# fpga.net
KiCad netlist of a schematic drawn in Altium Designer
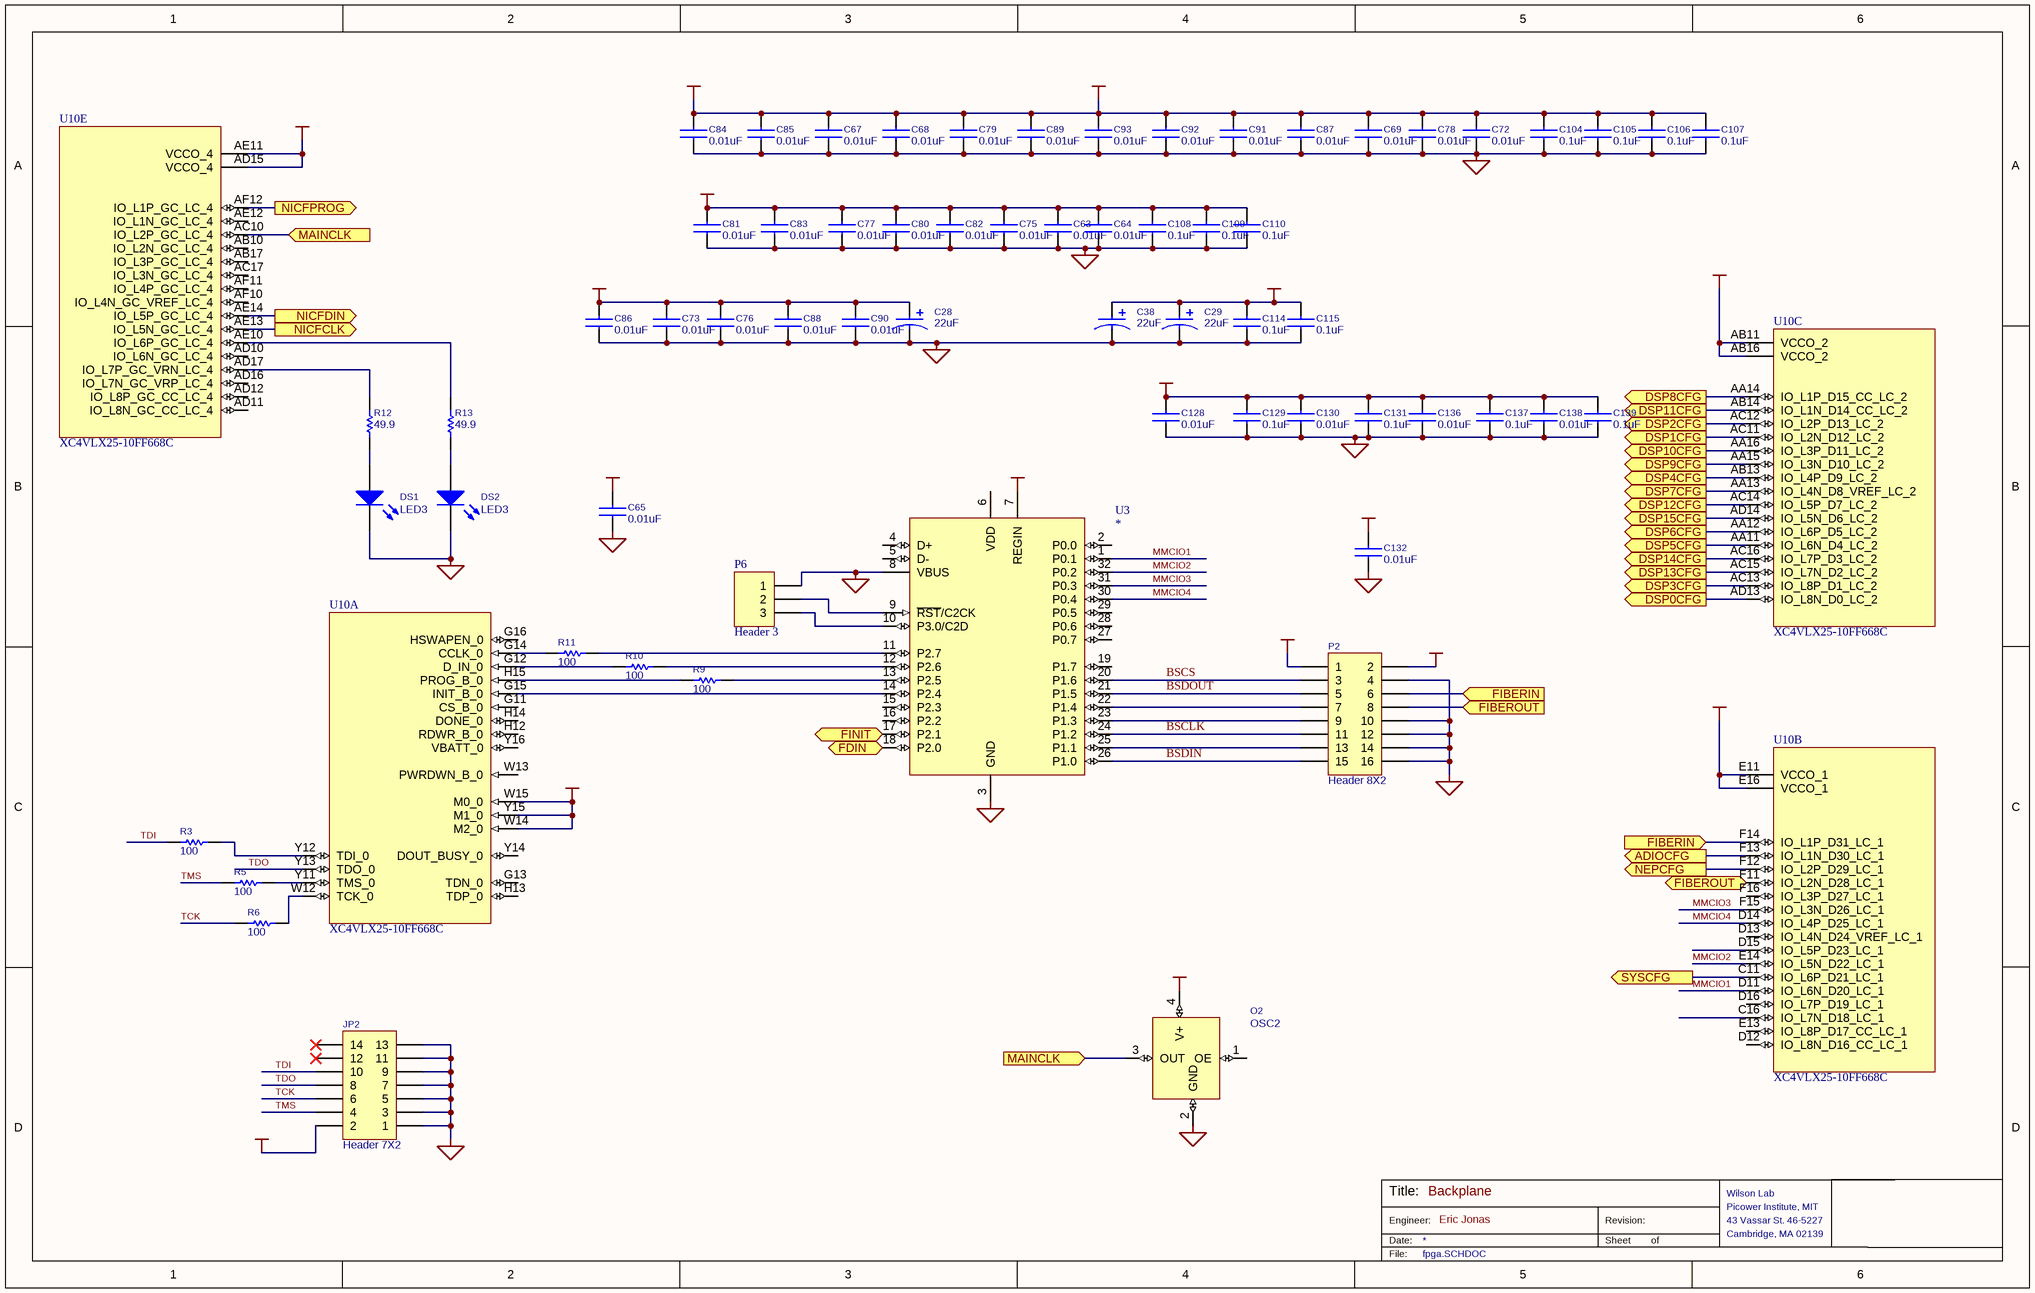
[diagram p0: fpga.SCHDOC]

(export (version "E")
  (design (tool "Eeschema 10.0.6"))
  (components
    (comp (ref "C28")
      (value "22uF")
      (footprint "6032")
      (description "Standard Capacitor")
      (fields (field (name "Comment") "POLCAP2"))
      (libsource (lib "parts") (part "POLCAP2"))
    )
    (comp (ref "C29")
      (value "22uF")
      (footprint "6032")
      (description "Standard Capacitor")
      (fields (field (name "Comment") "POLCAP2"))
      (libsource (lib "parts") (part "POLCAP2"))
    )
    (comp (ref "C38")
      (value "22uF")
      (footprint "6032")
      (description "Standard Capacitor")
      (fields (field (name "Comment") "POLCAP2"))
      (libsource (lib "parts") (part "POLCAP2"))
    )
    (comp (ref "C63")
      (value "0.01uF")
      (footprint "0402")
      (description "Standard Capacitor")
      (fields (field (name "Comment") "CAPACITOR"))
      (libsource (lib "parts") (part "CAPACITOR"))
    )
    (comp (ref "C64")
      (value "0.01uF")
      (footprint "0402")
      (description "Standard Capacitor")
      (fields (field (name "Comment") "CAPACITOR"))
      (libsource (lib "parts") (part "CAPACITOR"))
    )
    (comp (ref "C65")
      (value "0.01uF")
      (footprint "0402")
      (description "Standard Capacitor")
      (fields (field (name "Comment") "CAPACITOR"))
      (libsource (lib "parts") (part "CAPACITOR"))
    )
    (comp (ref "C67")
      (value "0.01uF")
      (footprint "0402")
      (description "Standard Capacitor")
      (fields (field (name "Comment") "CAPACITOR"))
      (libsource (lib "parts") (part "CAPACITOR"))
    )
    (comp (ref "C68")
      (value "0.01uF")
      (footprint "0402")
      (description "Standard Capacitor")
      (fields (field (name "Comment") "CAPACITOR"))
      (libsource (lib "parts") (part "CAPACITOR"))
    )
    (comp (ref "C69")
      (value "0.01uF")
      (footprint "0402")
      (description "Standard Capacitor")
      (fields (field (name "Comment") "CAPACITOR"))
      (libsource (lib "parts") (part "CAPACITOR"))
    )
    (comp (ref "C72")
      (value "0.01uF")
      (footprint "0402")
      (description "Standard Capacitor")
      (fields (field (name "Comment") "CAPACITOR"))
      (libsource (lib "parts") (part "CAPACITOR"))
    )
    (comp (ref "C73")
      (value "0.01uF")
      (footprint "0402")
      (description "Standard Capacitor")
      (fields (field (name "Comment") "CAPACITOR"))
      (libsource (lib "parts") (part "CAPACITOR"))
    )
    (comp (ref "C75")
      (value "0.01uF")
      (footprint "0402")
      (description "Standard Capacitor")
      (fields (field (name "Comment") "CAPACITOR"))
      (libsource (lib "parts") (part "CAPACITOR"))
    )
    (comp (ref "C76")
      (value "0.01uF")
      (footprint "0402")
      (description "Standard Capacitor")
      (fields (field (name "Comment") "CAPACITOR"))
      (libsource (lib "parts") (part "CAPACITOR"))
    )
    (comp (ref "C77")
      (value "0.01uF")
      (footprint "0402")
      (description "Standard Capacitor")
      (fields (field (name "Comment") "CAPACITOR"))
      (libsource (lib "parts") (part "CAPACITOR"))
    )
    (comp (ref "C78")
      (value "0.01uF")
      (footprint "0402")
      (description "Standard Capacitor")
      (fields (field (name "Comment") "CAPACITOR"))
      (libsource (lib "parts") (part "CAPACITOR"))
    )
    (comp (ref "C79")
      (value "0.01uF")
      (footprint "0402")
      (description "Standard Capacitor")
      (fields (field (name "Comment") "CAPACITOR"))
      (libsource (lib "parts") (part "CAPACITOR"))
    )
    (comp (ref "C80")
      (value "0.01uF")
      (footprint "0402")
      (description "Standard Capacitor")
      (fields (field (name "Comment") "CAPACITOR"))
      (libsource (lib "parts") (part "CAPACITOR"))
    )
    (comp (ref "C81")
      (value "0.01uF")
      (footprint "0402")
      (description "Standard Capacitor")
      (fields (field (name "Comment") "CAPACITOR"))
      (libsource (lib "parts") (part "CAPACITOR"))
    )
    (comp (ref "C82")
      (value "0.01uF")
      (footprint "0402")
      (description "Standard Capacitor")
      (fields (field (name "Comment") "CAPACITOR"))
      (libsource (lib "parts") (part "CAPACITOR"))
    )
    (comp (ref "C83")
      (value "0.01uF")
      (footprint "0402")
      (description "Standard Capacitor")
      (fields (field (name "Comment") "CAPACITOR"))
      (libsource (lib "parts") (part "CAPACITOR"))
    )
    (comp (ref "C84")
      (value "0.01uF")
      (footprint "0402")
      (description "Standard Capacitor")
      (fields (field (name "Comment") "CAPACITOR"))
      (libsource (lib "parts") (part "CAPACITOR"))
    )
    (comp (ref "C85")
      (value "0.01uF")
      (footprint "0402")
      (description "Standard Capacitor")
      (fields (field (name "Comment") "CAPACITOR"))
      (libsource (lib "parts") (part "CAPACITOR"))
    )
    (comp (ref "C86")
      (value "0.01uF")
      (footprint "0402")
      (description "Standard Capacitor")
      (fields (field (name "Comment") "CAPACITOR"))
      (libsource (lib "parts") (part "CAPACITOR"))
    )
    (comp (ref "C87")
      (value "0.01uF")
      (footprint "0402")
      (description "Standard Capacitor")
      (fields (field (name "Comment") "CAPACITOR"))
      (libsource (lib "parts") (part "CAPACITOR"))
    )
    (comp (ref "C88")
      (value "0.01uF")
      (footprint "0402")
      (description "Standard Capacitor")
      (fields (field (name "Comment") "CAPACITOR"))
      (libsource (lib "parts") (part "CAPACITOR"))
    )
    (comp (ref "C89")
      (value "0.01uF")
      (footprint "0402")
      (description "Standard Capacitor")
      (fields (field (name "Comment") "CAPACITOR"))
      (libsource (lib "parts") (part "CAPACITOR"))
    )
    (comp (ref "C90")
      (value "0.01uF")
      (footprint "0402")
      (description "Standard Capacitor")
      (fields (field (name "Comment") "CAPACITOR"))
      (libsource (lib "parts") (part "CAPACITOR"))
    )
    (comp (ref "C91")
      (value "0.01uF")
      (footprint "0402")
      (description "Standard Capacitor")
      (fields (field (name "Comment") "CAPACITOR"))
      (libsource (lib "parts") (part "CAPACITOR"))
    )
    (comp (ref "C92")
      (value "0.01uF")
      (footprint "0402")
      (description "Standard Capacitor")
      (fields (field (name "Comment") "CAPACITOR"))
      (libsource (lib "parts") (part "CAPACITOR"))
    )
    (comp (ref "C93")
      (value "0.01uF")
      (footprint "0402")
      (description "Standard Capacitor")
      (fields (field (name "Comment") "CAPACITOR"))
      (libsource (lib "parts") (part "CAPACITOR"))
    )
    (comp (ref "C104")
      (value "0.1uF")
      (footprint "0603")
      (description "Standard Capacitor")
      (fields (field (name "Comment") "CAPACITOR"))
      (libsource (lib "parts") (part "CAPACITOR"))
    )
    (comp (ref "C105")
      (value "0.1uF")
      (footprint "0603")
      (description "Standard Capacitor")
      (fields (field (name "Comment") "CAPACITOR"))
      (libsource (lib "parts") (part "CAPACITOR"))
    )
    (comp (ref "C106")
      (value "0.1uF")
      (footprint "0603")
      (description "Standard Capacitor")
      (fields (field (name "Comment") "CAPACITOR"))
      (libsource (lib "parts") (part "CAPACITOR"))
    )
    (comp (ref "C107")
      (value "0.1uF")
      (footprint "0603")
      (description "Standard Capacitor")
      (fields (field (name "Comment") "CAPACITOR"))
      (libsource (lib "parts") (part "CAPACITOR"))
    )
    (comp (ref "C108")
      (value "0.1uF")
      (footprint "0603")
      (description "Standard Capacitor")
      (fields (field (name "Comment") "CAPACITOR"))
      (libsource (lib "parts") (part "CAPACITOR"))
    )
    (comp (ref "C109")
      (value "0.1uF")
      (footprint "0603")
      (description "Standard Capacitor")
      (fields (field (name "Comment") "CAPACITOR"))
      (libsource (lib "parts") (part "CAPACITOR"))
    )
    (comp (ref "C110")
      (value "0.1uF")
      (footprint "0603")
      (description "Standard Capacitor")
      (fields (field (name "Comment") "CAPACITOR"))
      (libsource (lib "parts") (part "CAPACITOR"))
    )
    (comp (ref "C114")
      (value "0.1uF")
      (footprint "0603")
      (description "Standard Capacitor")
      (fields (field (name "Comment") "CAPACITOR"))
      (libsource (lib "parts") (part "CAPACITOR"))
    )
    (comp (ref "C115")
      (value "0.1uF")
      (footprint "0603")
      (description "Standard Capacitor")
      (fields (field (name "Comment") "CAPACITOR"))
      (libsource (lib "parts") (part "CAPACITOR"))
    )
    (comp (ref "C128")
      (value "0.01uF")
      (footprint "0402")
      (description "Standard Capacitor")
      (fields (field (name "Comment") "CAPACITOR"))
      (libsource (lib "parts") (part "CAPACITOR"))
    )
    (comp (ref "C129")
      (value "0.1uF")
      (footprint "0603")
      (description "Standard Capacitor")
      (fields (field (name "Comment") "CAPACITOR"))
      (libsource (lib "parts") (part "CAPACITOR"))
    )
    (comp (ref "C130")
      (value "0.01uF")
      (footprint "0402")
      (description "Standard Capacitor")
      (fields (field (name "Comment") "CAPACITOR"))
      (libsource (lib "parts") (part "CAPACITOR"))
    )
    (comp (ref "C131")
      (value "0.1uF")
      (footprint "0603")
      (description "Standard Capacitor")
      (fields (field (name "Comment") "CAPACITOR"))
      (libsource (lib "parts") (part "CAPACITOR"))
    )
    (comp (ref "C132")
      (value "0.01uF")
      (footprint "0402")
      (description "Standard Capacitor")
      (fields (field (name "Comment") "CAPACITOR"))
      (libsource (lib "parts") (part "CAPACITOR"))
    )
    (comp (ref "C136")
      (value "0.01uF")
      (footprint "0402")
      (description "Standard Capacitor")
      (fields (field (name "Comment") "CAPACITOR"))
      (libsource (lib "parts") (part "CAPACITOR"))
    )
    (comp (ref "C137")
      (value "0.1uF")
      (footprint "0603")
      (description "Standard Capacitor")
      (fields (field (name "Comment") "CAPACITOR"))
      (libsource (lib "parts") (part "CAPACITOR"))
    )
    (comp (ref "C138")
      (value "0.01uF")
      (footprint "0402")
      (description "Standard Capacitor")
      (fields (field (name "Comment") "CAPACITOR"))
      (libsource (lib "parts") (part "CAPACITOR"))
    )
    (comp (ref "C139")
      (value "0.1uF")
      (footprint "0603")
      (description "Standard Capacitor")
      (fields (field (name "Comment") "CAPACITOR"))
      (libsource (lib "parts") (part "CAPACITOR"))
    )
    (comp (ref "DS1")
      (value "LED3")
      (footprint "SMD _LED")
      (description "Typical BLUE SiC LED")
      (fields (field (name "PUBLISHER") "Altium Limited"))
      (libsource (lib "Miscellaneous Devices") (part "LED3"))
    )
    (comp (ref "DS2")
      (value "LED3")
      (footprint "SMD _LED")
      (description "Typical BLUE SiC LED")
      (fields (field (name "PUBLISHER") "Altium Limited"))
      (libsource (lib "Miscellaneous Devices") (part "LED3"))
    )
    (comp (ref "JP2")
      (value "Header 7X2")
      (footprint "SMT 2x7 2mm HDR")
      (description "Header, 7-Pin, Dual row")
      (fields (field (name "MANUFACTURER") "Generic Components") (field (name "PUBLISHER") "Altium Limited"))
      (libsource (lib "Miscellaneous Connectors") (part "Header 7X2"))
    )
    (comp (ref "O2")
      (value "OSC2")
      (footprint "ECS-3953M")
      (description "ECS SMD Oscillator, ECS-3953M")
      (fields (field (name "PART") "SG-636PCE 30.0000MC0"))
      (libsource (lib "parts") (part "OSC2"))
    )
    (comp (ref "P2")
      (value "Header 8X2")
      (footprint "MOLEX 15-91-2160")
      (description "Header, 8-Pin, Dual row")
      (fields (field (name "PUBLISHER") "Altium Limited"))
      (libsource (lib "parts") (part "Header 8X2"))
    )
    (comp (ref "P6")
      (value "Header 3")
      (footprint "HDR1X3")
      (description "Header, 3-Pin")
      (fields (field (name "PUBLISHER") "Altium Limited"))
      (libsource (lib "Miscellaneous Connectors") (part "Header 3"))
    )
    (comp (ref "R3")
      (value "100")
      (footprint "0603")
      (description "Standard Passive Resistor")
      (fields (field (name "TOLERANCE") "1%") (field (name "Comment") "current-limiting series res"))
      (libsource (lib "parts") (part "RESISTOR"))
    )
    (comp (ref "R5")
      (value "100")
      (footprint "0603")
      (description "Standard Passive Resistor")
      (fields (field (name "TOLERANCE") "1%") (field (name "Comment") "current-limiting series res"))
      (libsource (lib "parts") (part "RESISTOR"))
    )
    (comp (ref "R6")
      (value "100")
      (footprint "0603")
      (description "Standard Passive Resistor")
      (fields (field (name "TOLERANCE") "1%") (field (name "Comment") "current-limiting series res"))
      (libsource (lib "parts") (part "RESISTOR"))
    )
    (comp (ref "R9")
      (value "100")
      (footprint "0603")
      (description "Standard Passive Resistor")
      (fields (field (name "TOLERANCE") "1%") (field (name "Comment") "RESISTOR"))
      (libsource (lib "parts") (part "RESISTOR"))
    )
    (comp (ref "R10")
      (value "100")
      (footprint "0603")
      (description "Standard Passive Resistor")
      (fields (field (name "TOLERANCE") "1%") (field (name "Comment") "RESISTOR"))
      (libsource (lib "parts") (part "RESISTOR"))
    )
    (comp (ref "R11")
      (value "100")
      (footprint "0603")
      (description "Standard Passive Resistor")
      (fields (field (name "TOLERANCE") "1%") (field (name "Comment") "RESISTOR"))
      (libsource (lib "parts") (part "RESISTOR"))
    )
    (comp (ref "R12")
      (value "49.9")
      (footprint "0402")
      (description "Standard Passive Resistor")
      (fields (field (name "TOLERANCE") "1%") (field (name "Comment") "current-limiting series res"))
      (libsource (lib "parts") (part "RESISTOR"))
    )
    (comp (ref "R13")
      (value "49.9")
      (footprint "0402")
      (description "Standard Passive Resistor")
      (fields (field (name "TOLERANCE") "1%") (field (name "Comment") "current-limiting series res"))
      (libsource (lib "parts") (part "RESISTOR"))
    )
    (comp (ref "U3")
      (value "*")
      (footprint "QFP7x7-G32/N")
      (description "SiLiabs USB Micro")
      (libsource (lib "parts") (part "C8051F342/3/6/7"))
    )
    (comp (ref "U10")
      (value "XC4VLX25-10FF668C")
      (footprint "Xilinx FF668")
      (description "Xilinx Virtex-4")
      (libsource (lib "parts") (part "XC4VLX25-10FF668C"))
    )
  )
  (nets
    (net (code "1") (name "+0.9VCC") (class "Default") (node (ref "C132") (pin "1") (pintype "passive")))
    (net (code "2") (name "+1.2VCC") (class "Default")
      (node (ref "C28") (pin "1") (pintype "passive"))
      (node (ref "C73") (pin "1") (pintype "passive"))
      (node (ref "C76") (pin "1") (pintype "passive"))
      (node (ref "C86") (pin "1") (pintype "passive"))
      (node (ref "C88") (pin "1") (pintype "passive"))
      (node (ref "C90") (pin "1") (pintype "passive"))
    )
    (net (code "3") (name "+1.8VCC") (class "Default")
      (node (ref "C128") (pin "1") (pintype "passive"))
      (node (ref "C129") (pin "1") (pintype "passive"))
      (node (ref "C130") (pin "1") (pintype "passive"))
      (node (ref "C131") (pin "1") (pintype "passive"))
      (node (ref "C136") (pin "1") (pintype "passive"))
      (node (ref "C137") (pin "1") (pintype "passive"))
      (node (ref "C138") (pin "1") (pintype "passive"))
      (node (ref "C139") (pin "1") (pintype "passive"))
    )
    (net (code "4") (name "+2.5VCC") (class "Default")
      (node (ref "C104") (pin "1") (pintype "passive"))
      (node (ref "C105") (pin "1") (pintype "passive"))
      (node (ref "C106") (pin "1") (pintype "passive"))
      (node (ref "C107") (pin "1") (pintype "passive"))
      (node (ref "C114") (pin "1") (pintype "passive"))
      (node (ref "C115") (pin "1") (pintype "passive"))
      (node (ref "C29") (pin "1") (pintype "passive"))
      (node (ref "C38") (pin "1") (pintype "passive"))
      (node (ref "C67") (pin "1") (pintype "passive"))
      (node (ref "C68") (pin "1") (pintype "passive"))
      (node (ref "C69") (pin "1") (pintype "passive"))
      (node (ref "C72") (pin "1") (pintype "passive"))
      (node (ref "C78") (pin "1") (pintype "passive"))
      (node (ref "C79") (pin "1") (pintype "passive"))
      (node (ref "C84") (pin "1") (pintype "passive"))
      (node (ref "C85") (pin "1") (pintype "passive"))
      (node (ref "C87") (pin "1") (pintype "passive"))
      (node (ref "C89") (pin "1") (pintype "passive"))
      (node (ref "C91") (pin "1") (pintype "passive"))
      (node (ref "C92") (pin "1") (pintype "passive"))
      (node (ref "C93") (pin "1") (pintype "passive"))
    )
    (net (code "5") (name "+5VCC") (class "Default")
      (node (ref "C65") (pin "1") (pintype "passive"))
      (node (ref "P2") (pin "2") (pinfunction "2_2") (pintype "passive"))
      (node (ref "U3") (pin "7") (pinfunction "REGIN_7") (pintype "power_in"))
    )
    (net (code "6") (name "/ADIOCFG") (class "Default")
      (node (ref "U10") (pin "F13") (pinfunction "IO_L1N_D30_LC_1_F13") (pintype "bidirectional"))
    )
    (net (code "7") (name "/BSCLK") (class "Default")
      (node (ref "P2") (pin "11") (pinfunction "11_11") (pintype "passive"))
      (node (ref "U3") (pin "24") (pinfunction "P1.2_24") (pintype "bidirectional"))
    )
    (net (code "8") (name "/BSCS") (class "Default")
      (node (ref "P2") (pin "3") (pinfunction "3_3") (pintype "passive"))
      (node (ref "U3") (pin "20") (pinfunction "P1.6_20") (pintype "bidirectional"))
    )
    (net (code "9") (name "/BSDIN") (class "Default")
      (node (ref "P2") (pin "15") (pinfunction "15_15") (pintype "passive"))
      (node (ref "U3") (pin "26") (pinfunction "P1.0_26") (pintype "bidirectional"))
    )
    (net (code "10") (name "/BSDOUT") (class "Default")
      (node (ref "P2") (pin "5") (pinfunction "5_5") (pintype "passive"))
      (node (ref "U3") (pin "21") (pinfunction "P1.5_21") (pintype "bidirectional"))
    )
    (net (code "11") (name "/DSP0CFG") (class "Default")
      (node (ref "U10") (pin "AD13") (pinfunction "IO_L8N_D0_LC_2_AD13") (pintype "bidirectional"))
    )
    (net (code "12") (name "/DSP1CFG") (class "Default")
      (node (ref "U10") (pin "AC11") (pinfunction "IO_L2N_D12_LC_2_AC11") (pintype "bidirectional"))
    )
    (net (code "13") (name "/DSP2CFG") (class "Default")
      (node (ref "U10") (pin "AC12") (pinfunction "IO_L2P_D13_LC_2_AC12") (pintype "bidirectional"))
    )
    (net (code "14") (name "/DSP3CFG") (class "Default")
      (node (ref "U10") (pin "AC13") (pinfunction "IO_L8P_D1_LC_2_AC13") (pintype "bidirectional"))
    )
    (net (code "15") (name "/DSP4CFG") (class "Default")
      (node (ref "U10") (pin "AB13") (pinfunction "IO_L4P_D9_LC_2_AB13") (pintype "bidirectional"))
    )
    (net (code "16") (name "/DSP5CFG") (class "Default")
      (node (ref "U10") (pin "AA11") (pinfunction "IO_L6N_D4_LC_2_AA11") (pintype "bidirectional"))
    )
    (net (code "17") (name "/DSP6CFG") (class "Default")
      (node (ref "U10") (pin "AA12") (pinfunction "IO_L6P_D5_LC_2_AA12") (pintype "bidirectional"))
    )
    (net (code "18") (name "/DSP7CFG") (class "Default")
      (node (ref "U10") (pin "AA13") (pinfunction "IO_L4N_D8_VREF_LC_2_AA13") (pintype "bidirectional"))
    )
    (net (code "19") (name "/DSP8CFG") (class "Default")
      (node (ref "U10") (pin "AA14") (pinfunction "IO_L1P_D15_CC_LC_2_AA14") (pintype "bidirectional"))
    )
    (net (code "20") (name "/DSP9CFG") (class "Default")
      (node (ref "U10") (pin "AA15") (pinfunction "IO_L3N_D10_LC_2_AA15") (pintype "bidirectional"))
    )
    (net (code "21") (name "/DSP10CFG") (class "Default")
      (node (ref "U10") (pin "AA16") (pinfunction "IO_L3P_D11_LC_2_AA16") (pintype "bidirectional"))
    )
    (net (code "22") (name "/DSP11CFG") (class "Default")
      (node (ref "U10") (pin "AB14") (pinfunction "IO_L1N_D14_CC_LC_2_AB14") (pintype "bidirectional"))
    )
    (net (code "23") (name "/DSP12CFG") (class "Default")
      (node (ref "U10") (pin "AC14") (pinfunction "IO_L5P_D7_LC_2_AC14") (pintype "bidirectional"))
    )
    (net (code "24") (name "/DSP13CFG") (class "Default")
      (node (ref "U10") (pin "AC15") (pinfunction "IO_L7N_D2_LC_2_AC15") (pintype "bidirectional"))
    )
    (net (code "25") (name "/DSP14CFG") (class "Default")
      (node (ref "U10") (pin "AC16") (pinfunction "IO_L7P_D3_LC_2_AC16") (pintype "bidirectional"))
    )
    (net (code "26") (name "/DSP15CFG") (class "Default")
      (node (ref "U10") (pin "AD14") (pinfunction "IO_L5N_D6_LC_2_AD14") (pintype "bidirectional"))
    )
    (net (code "27") (name "/FDIN") (class "Default")
      (node (ref "U3") (pin "18") (pinfunction "P2.0_18") (pintype "bidirectional"))
    )
    (net (code "28") (name "/FIBERIN") (class "Default")
      (node (ref "P2") (pin "6") (pinfunction "6_6") (pintype "passive"))
      (node (ref "U10") (pin "F14") (pinfunction "IO_L1P_D31_LC_1_F14") (pintype "bidirectional"))
    )
    (net (code "29") (name "/FIBEROUT") (class "Default")
      (node (ref "P2") (pin "8") (pinfunction "8_8") (pintype "passive"))
      (node (ref "U10") (pin "F11") (pinfunction "IO_L2N_D28_LC_1_F11") (pintype "bidirectional"))
    )
    (net (code "30") (name "/FINIT") (class "Default")
      (node (ref "U3") (pin "17") (pinfunction "P2.1_17") (pintype "bidirectional"))
    )
    (net (code "31") (name "/MAINCLK") (class "Default")
      (node (ref "O2") (pin "3") (pinfunction "OUT_3") (pintype "bidirectional"))
      (node (ref "U10") (pin "AC10") (pinfunction "IO_L2P_GC_LC_4_AC10") (pintype "bidirectional"))
    )
    (net (code "32") (name "/MMCIO1") (class "Default")
      (node (ref "U10") (pin "D11") (pinfunction "IO_L6N_D20_LC_1_D11") (pintype "bidirectional"))
      (node (ref "U3") (pin "1") (pinfunction "P0.1_1") (pintype "bidirectional"))
    )
    (net (code "33") (name "/MMCIO2") (class "Default")
      (node (ref "U10") (pin "E14") (pinfunction "IO_L5N_D22_LC_1_E14") (pintype "bidirectional"))
      (node (ref "U3") (pin "32") (pinfunction "P0.2_32") (pintype "bidirectional"))
    )
    (net (code "34") (name "/MMCIO3") (class "Default")
      (node (ref "U10") (pin "F15") (pinfunction "IO_L3N_D26_LC_1_F15") (pintype "bidirectional"))
      (node (ref "U3") (pin "31") (pinfunction "P0.3_31") (pintype "bidirectional"))
    )
    (net (code "35") (name "/MMCIO4") (class "Default")
      (node (ref "U10") (pin "D14") (pinfunction "IO_L4P_D25_LC_1_D14") (pintype "bidirectional"))
      (node (ref "U3") (pin "30") (pinfunction "P0.4_30") (pintype "bidirectional"))
    )
    (net (code "36") (name "/NEPCFG") (class "Default")
      (node (ref "U10") (pin "F12") (pinfunction "IO_L2P_D29_LC_1_F12") (pintype "bidirectional"))
    )
    (net (code "37") (name "/NICFCLK") (class "Default")
      (node (ref "U10") (pin "AE13") (pinfunction "IO_L5N_GC_LC_4_AE13") (pintype "bidirectional"))
    )
    (net (code "38") (name "/NICFDIN") (class "Default")
      (node (ref "U10") (pin "AE14") (pinfunction "IO_L5P_GC_LC_4_AE14") (pintype "bidirectional"))
    )
    (net (code "39") (name "/NICFPROG") (class "Default")
      (node (ref "U10") (pin "AF12") (pinfunction "IO_L1P_GC_LC_4_AF12") (pintype "bidirectional"))
    )
    (net (code "40") (name "/SYSCFG") (class "Default")
      (node (ref "U10") (pin "C11") (pinfunction "IO_L6P_D21_LC_1_C11") (pintype "bidirectional"))
    )
    (net (code "41") (name "/TCK") (class "Default")
      (node (ref "JP2") (pin "6") (pinfunction "6_6") (pintype "passive"))
      (node (ref "R6") (pin "1") (pintype "passive"))
    )
    (net (code "42") (name "/TDI") (class "Default")
      (node (ref "JP2") (pin "10") (pinfunction "10_10") (pintype "passive"))
      (node (ref "R3") (pin "2") (pintype "passive"))
    )
    (net (code "43") (name "/TDO") (class "Default")
      (node (ref "JP2") (pin "8") (pinfunction "8_8") (pintype "passive"))
      (node (ref "U10") (pin "Y13") (pinfunction "TDO_0_Y13") (pintype "bidirectional"))
    )
    (net (code "44") (name "/TMS") (class "Default")
      (node (ref "JP2") (pin "4") (pinfunction "4_4") (pintype "passive"))
      (node (ref "R5") (pin "2") (pintype "passive"))
    )
    (net (code "45") (name "GND") (class "Default")
      (node (ref "C104") (pin "2") (pintype "passive"))
      (node (ref "C105") (pin "2") (pintype "passive"))
      (node (ref "C106") (pin "2") (pintype "passive"))
      (node (ref "C107") (pin "2") (pintype "passive"))
      (node (ref "C108") (pin "2") (pintype "passive"))
      (node (ref "C109") (pin "2") (pintype "passive"))
      (node (ref "C110") (pin "2") (pintype "passive"))
      (node (ref "C114") (pin "2") (pintype "passive"))
      (node (ref "C115") (pin "2") (pintype "passive"))
      (node (ref "C128") (pin "2") (pintype "passive"))
      (node (ref "C129") (pin "2") (pintype "passive"))
      (node (ref "C130") (pin "2") (pintype "passive"))
      (node (ref "C131") (pin "2") (pintype "passive"))
      (node (ref "C132") (pin "2") (pintype "passive"))
      (node (ref "C136") (pin "2") (pintype "passive"))
      (node (ref "C137") (pin "2") (pintype "passive"))
      (node (ref "C138") (pin "2") (pintype "passive"))
      (node (ref "C139") (pin "2") (pintype "passive"))
      (node (ref "C28") (pin "2") (pintype "passive"))
      (node (ref "C29") (pin "2") (pintype "passive"))
      (node (ref "C38") (pin "2") (pintype "passive"))
      (node (ref "C63") (pin "2") (pintype "passive"))
      (node (ref "C64") (pin "2") (pintype "passive"))
      (node (ref "C65") (pin "2") (pintype "passive"))
      (node (ref "C67") (pin "2") (pintype "passive"))
      (node (ref "C68") (pin "2") (pintype "passive"))
      (node (ref "C69") (pin "2") (pintype "passive"))
      (node (ref "C72") (pin "2") (pintype "passive"))
      (node (ref "C73") (pin "2") (pintype "passive"))
      (node (ref "C75") (pin "2") (pintype "passive"))
      (node (ref "C76") (pin "2") (pintype "passive"))
      (node (ref "C77") (pin "2") (pintype "passive"))
      (node (ref "C78") (pin "2") (pintype "passive"))
      (node (ref "C79") (pin "2") (pintype "passive"))
      (node (ref "C80") (pin "2") (pintype "passive"))
      (node (ref "C81") (pin "2") (pintype "passive"))
      (node (ref "C82") (pin "2") (pintype "passive"))
      (node (ref "C83") (pin "2") (pintype "passive"))
      (node (ref "C84") (pin "2") (pintype "passive"))
      (node (ref "C85") (pin "2") (pintype "passive"))
      (node (ref "C86") (pin "2") (pintype "passive"))
      (node (ref "C87") (pin "2") (pintype "passive"))
      (node (ref "C88") (pin "2") (pintype "passive"))
      (node (ref "C89") (pin "2") (pintype "passive"))
      (node (ref "C90") (pin "2") (pintype "passive"))
      (node (ref "C91") (pin "2") (pintype "passive"))
      (node (ref "C92") (pin "2") (pintype "passive"))
      (node (ref "C93") (pin "2") (pintype "passive"))
      (node (ref "DS1") (pin "2") (pinfunction "K_2") (pintype "passive"))
      (node (ref "DS2") (pin "2") (pinfunction "K_2") (pintype "passive"))
      (node (ref "JP2") (pin "1") (pinfunction "1_1") (pintype "passive"))
      (node (ref "JP2") (pin "11") (pinfunction "11_11") (pintype "passive"))
      (node (ref "JP2") (pin "13") (pinfunction "13_13") (pintype "passive"))
      (node (ref "JP2") (pin "3") (pinfunction "3_3") (pintype "passive"))
      (node (ref "JP2") (pin "5") (pinfunction "5_5") (pintype "passive"))
      (node (ref "JP2") (pin "7") (pinfunction "7_7") (pintype "passive"))
      (node (ref "JP2") (pin "9") (pinfunction "9_9") (pintype "passive"))
      (node (ref "O2") (pin "2") (pinfunction "GND_2") (pintype "bidirectional"))
      (node (ref "P2") (pin "10") (pinfunction "10_10") (pintype "passive"))
      (node (ref "P2") (pin "12") (pinfunction "12_12") (pintype "passive"))
      (node (ref "P2") (pin "14") (pinfunction "14_14") (pintype "passive"))
      (node (ref "P2") (pin "16") (pinfunction "16_16") (pintype "passive"))
      (node (ref "P2") (pin "4") (pinfunction "4_4") (pintype "passive"))
      (node (ref "P6") (pin "1") (pinfunction "1_1") (pintype "passive"))
      (node (ref "U3") (pin "3") (pinfunction "GND_3") (pintype "power_in"))
      (node (ref "U3") (pin "8") (pinfunction "VBUS_8") (pintype "power_in"))
    )
    (net (code "46") (name "Net-(DS1-A)") (class "Default")
      (node (ref "DS1") (pin "1") (pinfunction "A_1") (pintype "passive"))
      (node (ref "R12") (pin "2") (pintype "passive"))
    )
    (net (code "47") (name "Net-(DS2-A)") (class "Default")
      (node (ref "DS2") (pin "1") (pinfunction "A_1") (pintype "passive"))
      (node (ref "R13") (pin "2") (pintype "passive"))
    )
    (net (code "48") (name "Net-(U3-P1.1)") (class "Default")
      (node (ref "P2") (pin "13") (pinfunction "13_13") (pintype "passive"))
      (node (ref "U3") (pin "25") (pinfunction "P1.1_25") (pintype "bidirectional"))
    )
    (net (code "49") (name "Net-(U3-P1.3)") (class "Default")
      (node (ref "P2") (pin "9") (pinfunction "9_9") (pintype "passive"))
      (node (ref "U3") (pin "23") (pinfunction "P1.3_23") (pintype "bidirectional"))
    )
    (net (code "50") (name "Net-(U3-P1.4)") (class "Default")
      (node (ref "P2") (pin "7") (pinfunction "7_7") (pintype "passive"))
      (node (ref "U3") (pin "22") (pinfunction "P1.4_22") (pintype "bidirectional"))
    )
    (net (code "51") (name "Net-(U3-P2.5)") (class "Default")
      (node (ref "R9") (pin "1") (pintype "passive"))
      (node (ref "U3") (pin "13") (pinfunction "P2.5_13") (pintype "bidirectional"))
    )
    (net (code "52") (name "Net-(U3-P2.6)") (class "Default")
      (node (ref "R10") (pin "1") (pintype "passive"))
      (node (ref "U3") (pin "12") (pinfunction "P2.6_12") (pintype "bidirectional"))
    )
    (net (code "53") (name "Net-(U3-P2.7)") (class "Default")
      (node (ref "R11") (pin "1") (pintype "passive"))
      (node (ref "U3") (pin "11") (pinfunction "P2.7_11") (pintype "bidirectional"))
    )
    (net (code "54") (name "Net-(U3-P3.0{slash}C2D)") (class "Default")
      (node (ref "P6") (pin "3") (pinfunction "3_3") (pintype "passive"))
      (node (ref "U3") (pin "10") (pinfunction "P3.0/C2D_10") (pintype "bidirectional"))
    )
    (net (code "55") (name "Net-(U3-~{RST}{slash}C2CK)") (class "Default")
      (node (ref "P6") (pin "2") (pinfunction "2_2") (pintype "passive"))
      (node (ref "U3") (pin "9") (pinfunction "~{RST}/C2CK_9") (pintype "input"))
    )
    (net (code "56") (name "Net-(U10A-CCLK_0)") (class "Default")
      (node (ref "R11") (pin "2") (pintype "passive"))
      (node (ref "U10") (pin "G14") (pinfunction "CCLK_0_G14") (pintype "input"))
    )
    (net (code "57") (name "Net-(U10A-D_IN_0)") (class "Default")
      (node (ref "R10") (pin "2") (pintype "passive"))
      (node (ref "U10") (pin "G12") (pinfunction "D_IN_0_G12") (pintype "input"))
    )
    (net (code "58") (name "Net-(U10A-INIT_B_0)") (class "Default")
      (node (ref "U10") (pin "G15") (pinfunction "INIT_B_0_G15") (pintype "input"))
      (node (ref "U3") (pin "14") (pinfunction "P2.4_14") (pintype "bidirectional"))
    )
    (net (code "59") (name "Net-(U10A-PROG_B_0)") (class "Default")
      (node (ref "R9") (pin "2") (pintype "passive"))
      (node (ref "U10") (pin "H15") (pinfunction "PROG_B_0_H15") (pintype "input"))
    )
    (net (code "60") (name "Net-(U10A-TCK_0)") (class "Default")
      (node (ref "R6") (pin "2") (pintype "passive"))
      (node (ref "U10") (pin "W12") (pinfunction "TCK_0_W12") (pintype "bidirectional"))
    )
    (net (code "61") (name "Net-(U10A-TDI_0)") (class "Default")
      (node (ref "R3") (pin "1") (pintype "passive"))
      (node (ref "U10") (pin "Y12") (pinfunction "TDI_0_Y12") (pintype "bidirectional"))
    )
    (net (code "62") (name "Net-(U10A-TMS_0)") (class "Default")
      (node (ref "R5") (pin "1") (pintype "passive"))
      (node (ref "U10") (pin "Y11") (pinfunction "TMS_0_Y11") (pintype "bidirectional"))
    )
    (net (code "63") (name "Net-(U10E-IO_L6P_GC_LC_4)") (class "Default")
      (node (ref "R13") (pin "1") (pintype "passive"))
      (node (ref "U10") (pin "AE10") (pinfunction "IO_L6P_GC_LC_4_AE10") (pintype "bidirectional"))
    )
    (net (code "64") (name "Net-(U10E-IO_L7P_GC_VRN_LC_4)") (class "Default")
      (node (ref "R12") (pin "1") (pintype "passive"))
      (node (ref "U10") (pin "AD17") (pinfunction "IO_L7P_GC_VRN_LC_4_AD17") (pintype "bidirectional"))
    )
    (net (code "65") (name "VCC") (class "Default")
      (node (ref "C108") (pin "1") (pintype "passive"))
      (node (ref "C109") (pin "1") (pintype "passive"))
      (node (ref "C110") (pin "1") (pintype "passive"))
      (node (ref "C63") (pin "1") (pintype "passive"))
      (node (ref "C64") (pin "1") (pintype "passive"))
      (node (ref "C75") (pin "1") (pintype "passive"))
      (node (ref "C77") (pin "1") (pintype "passive"))
      (node (ref "C80") (pin "1") (pintype "passive"))
      (node (ref "C81") (pin "1") (pintype "passive"))
      (node (ref "C82") (pin "1") (pintype "passive"))
      (node (ref "C83") (pin "1") (pintype "passive"))
      (node (ref "JP2") (pin "2") (pinfunction "2_2") (pintype "passive"))
      (node (ref "O2") (pin "4") (pinfunction "V+_4") (pintype "bidirectional"))
      (node (ref "P2") (pin "1") (pinfunction "1_1") (pintype "passive"))
      (node (ref "U10") (pin "AB11") (pinfunction "VCCO_2_AB11") (pintype "power_in"))
      (node (ref "U10") (pin "AB16") (pinfunction "VCCO_2_AB16") (pintype "power_in"))
      (node (ref "U10") (pin "AD15") (pinfunction "VCCO_4_AD15") (pintype "power_in"))
      (node (ref "U10") (pin "AE11") (pinfunction "VCCO_4_AE11") (pintype "power_in"))
      (node (ref "U10") (pin "E11") (pinfunction "VCCO_1_E11") (pintype "power_in"))
      (node (ref "U10") (pin "E16") (pinfunction "VCCO_1_E16") (pintype "power_in"))
      (node (ref "U10") (pin "W14") (pinfunction "M2_0_W14") (pintype "input"))
      (node (ref "U10") (pin "W15") (pinfunction "M0_0_W15") (pintype "input"))
      (node (ref "U10") (pin "Y15") (pinfunction "M1_0_Y15") (pintype "input"))
    )
    (net (code "66") (name "unconnected-(JP2-Pad12)") (class "Default")
      (node (ref "JP2") (pin "12") (pinfunction "12_12") (pintype "passive+no_connect"))
    )
    (net (code "67") (name "unconnected-(JP2-Pad14)") (class "Default")
      (node (ref "JP2") (pin "14") (pinfunction "14_14") (pintype "passive+no_connect"))
    )
    (net (code "68") (name "unconnected-(O2-OE-Pad1)") (class "Default")
      (node (ref "O2") (pin "1") (pinfunction "OE_1") (pintype "bidirectional"))
    )
    (net (code "69") (name "unconnected-(U3-D+-Pad4)") (class "Default")
      (node (ref "U3") (pin "4") (pinfunction "D+_4") (pintype "bidirectional"))
    )
    (net (code "70") (name "unconnected-(U3-D--Pad5)") (class "Default")
      (node (ref "U3") (pin "5") (pinfunction "D-_5") (pintype "bidirectional"))
    )
    (net (code "71") (name "unconnected-(U3-P0.0-Pad2)") (class "Default")
      (node (ref "U3") (pin "2") (pinfunction "P0.0_2") (pintype "bidirectional"))
    )
    (net (code "72") (name "unconnected-(U3-P0.5-Pad29)") (class "Default")
      (node (ref "U3") (pin "29") (pinfunction "P0.5_29") (pintype "bidirectional"))
    )
    (net (code "73") (name "unconnected-(U3-P0.6-Pad28)") (class "Default")
      (node (ref "U3") (pin "28") (pinfunction "P0.6_28") (pintype "bidirectional"))
    )
    (net (code "74") (name "unconnected-(U3-P0.7-Pad27)") (class "Default")
      (node (ref "U3") (pin "27") (pinfunction "P0.7_27") (pintype "bidirectional"))
    )
    (net (code "75") (name "unconnected-(U3-P1.7-Pad19)") (class "Default")
      (node (ref "U3") (pin "19") (pinfunction "P1.7_19") (pintype "bidirectional"))
    )
    (net (code "76") (name "unconnected-(U3-P2.2-Pad16)") (class "Default")
      (node (ref "U3") (pin "16") (pinfunction "P2.2_16") (pintype "bidirectional"))
    )
    (net (code "77") (name "unconnected-(U3-P2.3-Pad15)") (class "Default")
      (node (ref "U3") (pin "15") (pinfunction "P2.3_15") (pintype "bidirectional"))
    )
    (net (code "78") (name "unconnected-(U3-VDD-Pad6)") (class "Default")
      (node (ref "U3") (pin "6") (pinfunction "VDD_6") (pintype "power_in"))
    )
    (net (code "79") (name "unconnected-(U10A-CS_B_0-PadG11)") (class "Default")
      (node (ref "U10") (pin "G11") (pinfunction "CS_B_0_G11") (pintype "input"))
    )
    (net (code "80") (name "unconnected-(U10A-DONE_0-PadH14)") (class "Default")
      (node (ref "U10") (pin "H14") (pinfunction "DONE_0_H14") (pintype "bidirectional"))
    )
    (net (code "81") (name "unconnected-(U10A-DOUT_BUSY_0-PadY14)") (class "Default")
      (node (ref "U10") (pin "Y14") (pinfunction "DOUT_BUSY_0_Y14") (pintype "bidirectional"))
    )
    (net (code "82") (name "unconnected-(U10A-HSWAPEN_0-PadG16)") (class "Default")
      (node (ref "U10") (pin "G16") (pinfunction "HSWAPEN_0_G16") (pintype "bidirectional"))
    )
    (net (code "83") (name "unconnected-(U10A-PWRDWN_B_0-PadW13)") (class "Default")
      (node (ref "U10") (pin "W13") (pinfunction "PWRDWN_B_0_W13") (pintype "input"))
    )
    (net (code "84") (name "unconnected-(U10A-RDWR_B_0-PadH12)") (class "Default")
      (node (ref "U10") (pin "H12") (pinfunction "RDWR_B_0_H12") (pintype "bidirectional"))
    )
    (net (code "85") (name "unconnected-(U10A-TDN_0-PadG13)") (class "Default")
      (node (ref "U10") (pin "G13") (pinfunction "TDN_0_G13") (pintype "bidirectional"))
    )
    (net (code "86") (name "unconnected-(U10A-TDP_0-PadH13)") (class "Default")
      (node (ref "U10") (pin "H13") (pinfunction "TDP_0_H13") (pintype "bidirectional"))
    )
    (net (code "87") (name "unconnected-(U10A-VBATT_0-PadY16)") (class "Default")
      (node (ref "U10") (pin "Y16") (pinfunction "VBATT_0_Y16") (pintype "bidirectional"))
    )
    (net (code "88") (name "unconnected-(U10B-IO_L3P_D27_LC_1-PadF16)") (class "Default")
      (node (ref "U10") (pin "F16") (pinfunction "IO_L3P_D27_LC_1_F16") (pintype "bidirectional"))
    )
    (net (code "89") (name "unconnected-(U10B-IO_L4N_D24_VREF_LC_1-PadD13)") (class "Default")
      (node (ref "U10") (pin "D13") (pinfunction "IO_L4N_D24_VREF_LC_1_D13") (pintype "bidirectional"))
    )
    (net (code "90") (name "unconnected-(U10B-IO_L5P_D23_LC_1-PadD15)") (class "Default")
      (node (ref "U10") (pin "D15") (pinfunction "IO_L5P_D23_LC_1_D15") (pintype "bidirectional"))
    )
    (net (code "91") (name "unconnected-(U10B-IO_L7N_D18_LC_1-PadC16)") (class "Default")
      (node (ref "U10") (pin "C16") (pinfunction "IO_L7N_D18_LC_1_C16") (pintype "bidirectional"))
    )
    (net (code "92") (name "unconnected-(U10B-IO_L7P_D19_LC_1-PadD16)") (class "Default")
      (node (ref "U10") (pin "D16") (pinfunction "IO_L7P_D19_LC_1_D16") (pintype "bidirectional"))
    )
    (net (code "93") (name "unconnected-(U10B-IO_L8N_D16_CC_LC_1-PadD12)") (class "Default")
      (node (ref "U10") (pin "D12") (pinfunction "IO_L8N_D16_CC_LC_1_D12") (pintype "bidirectional"))
    )
    (net (code "94") (name "unconnected-(U10B-IO_L8P_D17_CC_LC_1-PadE13)") (class "Default")
      (node (ref "U10") (pin "E13") (pinfunction "IO_L8P_D17_CC_LC_1_E13") (pintype "bidirectional"))
    )
    (net (code "95") (name "unconnected-(U10E-IO_L1N_GC_LC_4-PadAE12)") (class "Default")
      (node (ref "U10") (pin "AE12") (pinfunction "IO_L1N_GC_LC_4_AE12") (pintype "bidirectional"))
    )
    (net (code "96") (name "unconnected-(U10E-IO_L2N_GC_LC_4-PadAB10)") (class "Default")
      (node (ref "U10") (pin "AB10") (pinfunction "IO_L2N_GC_LC_4_AB10") (pintype "bidirectional"))
    )
    (net (code "97") (name "unconnected-(U10E-IO_L3N_GC_LC_4-PadAC17)") (class "Default")
      (node (ref "U10") (pin "AC17") (pinfunction "IO_L3N_GC_LC_4_AC17") (pintype "bidirectional"))
    )
    (net (code "98") (name "unconnected-(U10E-IO_L3P_GC_LC_4-PadAB17)") (class "Default")
      (node (ref "U10") (pin "AB17") (pinfunction "IO_L3P_GC_LC_4_AB17") (pintype "bidirectional"))
    )
    (net (code "99") (name "unconnected-(U10E-IO_L4N_GC_VREF_LC_4-PadAF10)") (class "Default")
      (node (ref "U10") (pin "AF10") (pinfunction "IO_L4N_GC_VREF_LC_4_AF10") (pintype "bidirectional"))
    )
    (net (code "100") (name "unconnected-(U10E-IO_L4P_GC_LC_4-PadAF11)") (class "Default")
      (node (ref "U10") (pin "AF11") (pinfunction "IO_L4P_GC_LC_4_AF11") (pintype "bidirectional"))
    )
    (net (code "101") (name "unconnected-(U10E-IO_L6N_GC_LC_4-PadAD10)") (class "Default")
      (node (ref "U10") (pin "AD10") (pinfunction "IO_L6N_GC_LC_4_AD10") (pintype "bidirectional"))
    )
    (net (code "102") (name "unconnected-(U10E-IO_L7N_GC_VRP_LC_4-PadAD16)") (class "Default")
      (node (ref "U10") (pin "AD16") (pinfunction "IO_L7N_GC_VRP_LC_4_AD16") (pintype "bidirectional"))
    )
    (net (code "103") (name "unconnected-(U10E-IO_L8N_GC_CC_LC_4-PadAD11)") (class "Default")
      (node (ref "U10") (pin "AD11") (pinfunction "IO_L8N_GC_CC_LC_4_AD11") (pintype "bidirectional"))
    )
    (net (code "104") (name "unconnected-(U10E-IO_L8P_GC_CC_LC_4-PadAD12)") (class "Default")
      (node (ref "U10") (pin "AD12") (pinfunction "IO_L8P_GC_CC_LC_4_AD12") (pintype "bidirectional"))
    )
  )
)
